# Sheet1.net
KiCad netlist of a schematic drawn in Altium Designer
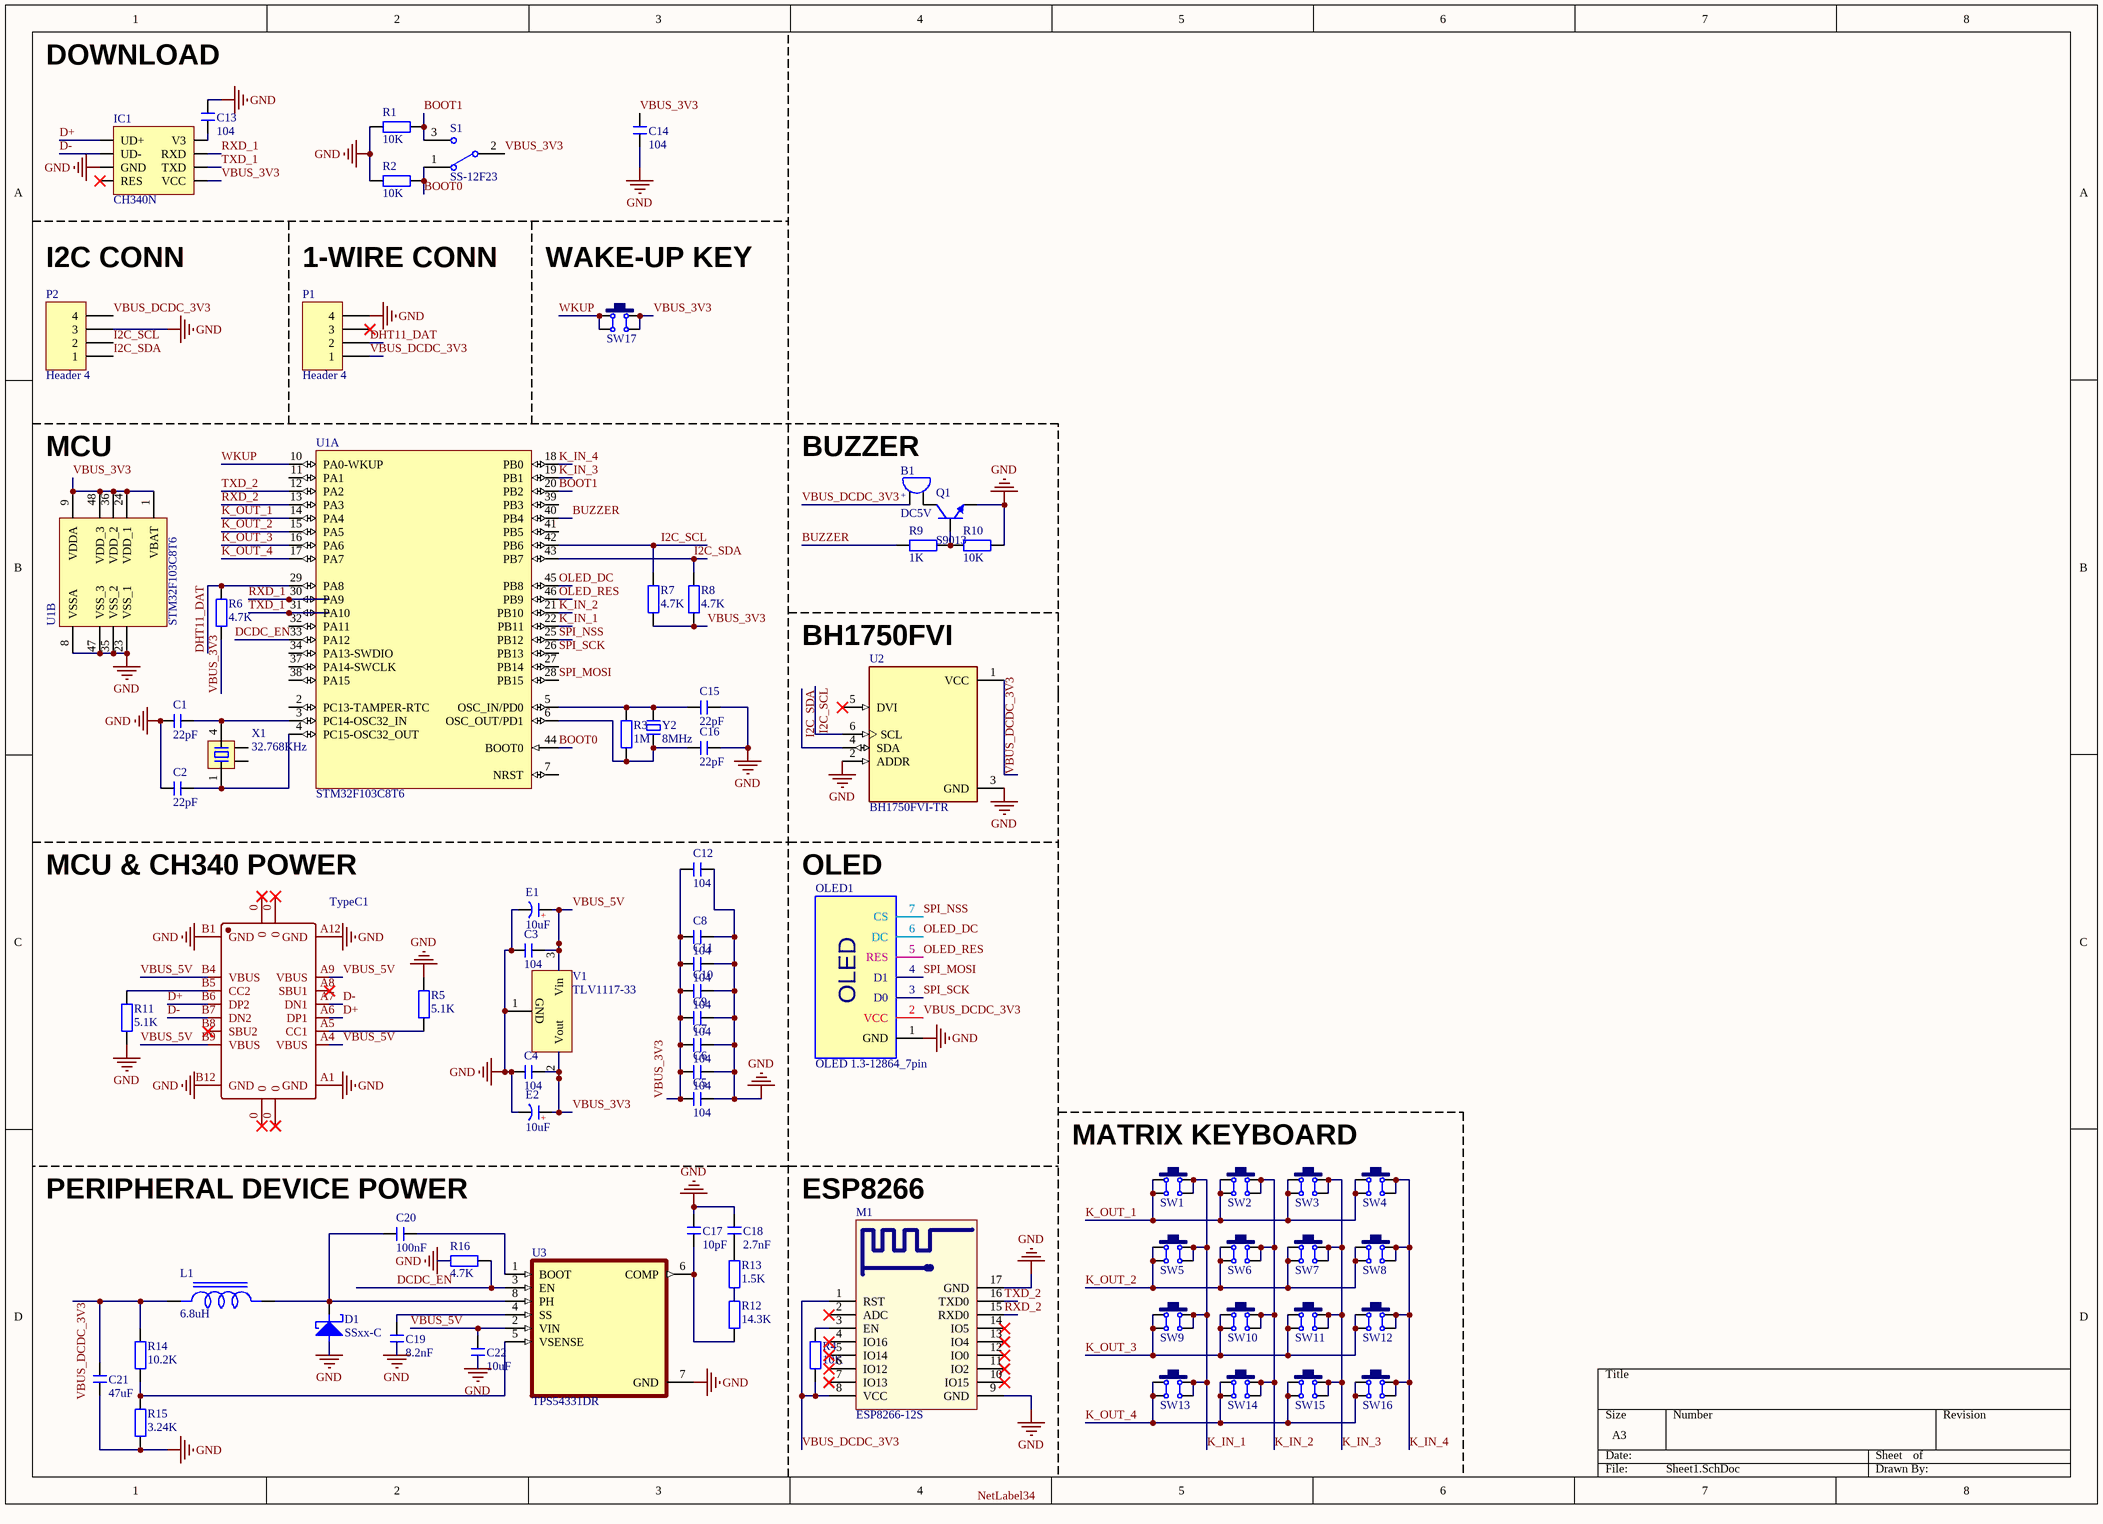
[diagram p0: Sheet1.SchDoc]

(export (version "E")
  (design (tool "Eeschema 10.0.6"))
  (components
    (comp (ref "B1")
      (value "DC5V")
      (footprint "BEEP 5x9x5.5")
      (description "蜂鸣器")
      (fields (field (name "版权归属") "黎明电子style"))
      (libsource (lib "基地硬件部AD库3.01") (part "BEEP"))
    )
    (comp (ref "C1")
      (value "22pF")
      (footprint "C 0805")
      (description "无极性贴片电容")
      (fields (field (name "版权归属") "黎明电子style"))
      (libsource (lib "基地硬件部AD库3.01") (part "C"))
    )
    (comp (ref "C2")
      (value "22pF")
      (footprint "C 0805")
      (description "无极性贴片电容")
      (fields (field (name "版权归属") "黎明电子style"))
      (libsource (lib "基地硬件部AD库3.01") (part "C"))
    )
    (comp (ref "C3")
      (value "104")
      (footprint "C 0805")
      (description "无极性贴片电容")
      (fields (field (name "版权归属") "黎明电子style"))
      (libsource (lib "基地硬件部AD库3.01") (part "C"))
    )
    (comp (ref "C4")
      (value "104")
      (footprint "C 0805")
      (description "无极性贴片电容")
      (fields (field (name "版权归属") "黎明电子style"))
      (libsource (lib "基地硬件部AD库3.01") (part "C"))
    )
    (comp (ref "C5")
      (value "104")
      (footprint "C 0805")
      (description "无极性贴片电容")
      (fields (field (name "版权归属") "黎明电子style"))
      (libsource (lib "基地硬件部AD库3.01") (part "C"))
    )
    (comp (ref "C6")
      (value "104")
      (footprint "C 0805")
      (description "无极性贴片电容")
      (fields (field (name "版权归属") "黎明电子style"))
      (libsource (lib "基地硬件部AD库3.01") (part "C"))
    )
    (comp (ref "C7")
      (value "104")
      (footprint "C 0805")
      (description "无极性贴片电容")
      (fields (field (name "版权归属") "黎明电子style"))
      (libsource (lib "基地硬件部AD库3.01") (part "C"))
    )
    (comp (ref "C8")
      (value "104")
      (footprint "C 0805")
      (description "无极性贴片电容")
      (fields (field (name "版权归属") "黎明电子style"))
      (libsource (lib "基地硬件部AD库3.01") (part "C"))
    )
    (comp (ref "C9")
      (value "104")
      (footprint "C 0805")
      (description "无极性贴片电容")
      (fields (field (name "版权归属") "黎明电子style"))
      (libsource (lib "基地硬件部AD库3.01") (part "C"))
    )
    (comp (ref "C10")
      (value "104")
      (footprint "C 0805")
      (description "无极性贴片电容")
      (fields (field (name "版权归属") "黎明电子style"))
      (libsource (lib "基地硬件部AD库3.01") (part "C"))
    )
    (comp (ref "C11")
      (value "104")
      (footprint "C 0805")
      (description "无极性贴片电容")
      (fields (field (name "版权归属") "黎明电子style"))
      (libsource (lib "基地硬件部AD库3.01") (part "C"))
    )
    (comp (ref "C12")
      (value "104")
      (footprint "C 0805")
      (description "无极性贴片电容")
      (fields (field (name "版权归属") "黎明电子style"))
      (libsource (lib "基地硬件部AD库3.01") (part "C"))
    )
    (comp (ref "C13")
      (value "104")
      (footprint "C 0805")
      (description "无极性贴片电容")
      (fields (field (name "版权归属") "黎明电子style"))
      (libsource (lib "基地硬件部AD库3.01") (part "C"))
    )
    (comp (ref "C14")
      (value "104")
      (footprint "C 0805")
      (description "无极性贴片电容")
      (fields (field (name "版权归属") "黎明电子style"))
      (libsource (lib "基地硬件部AD库3.01") (part "C"))
    )
    (comp (ref "C15")
      (value "22pF")
      (footprint "C 0805")
      (description "无极性贴片电容")
      (fields (field (name "版权归属") "黎明电子style"))
      (libsource (lib "基地硬件部AD库3.01") (part "C"))
    )
    (comp (ref "C16")
      (value "22pF")
      (footprint "C 0805")
      (description "无极性贴片电容")
      (fields (field (name "版权归属") "黎明电子style"))
      (libsource (lib "基地硬件部AD库3.01") (part "C"))
    )
    (comp (ref "C17")
      (value "10pF")
      (footprint "C 0805")
      (description "无极性贴片电容")
      (fields (field (name "版权归属") "黎明电子style"))
      (libsource (lib "基地硬件部AD库3.01") (part "C"))
    )
    (comp (ref "C18")
      (value "2.7nF")
      (footprint "C 0805")
      (description "无极性贴片电容")
      (fields (field (name "版权归属") "黎明电子style"))
      (libsource (lib "基地硬件部AD库3.01") (part "C"))
    )
    (comp (ref "C19")
      (value "8.2nF")
      (footprint "C 0805")
      (description "无极性贴片电容")
      (fields (field (name "版权归属") "黎明电子style"))
      (libsource (lib "基地硬件部AD库3.01") (part "C"))
    )
    (comp (ref "C20")
      (value "100nF")
      (footprint "C 0805")
      (description "无极性贴片电容")
      (fields (field (name "版权归属") "黎明电子style"))
      (libsource (lib "基地硬件部AD库3.01") (part "C"))
    )
    (comp (ref "C21")
      (value "47uF")
      (footprint "C 0805")
      (description "无极性贴片电容")
      (fields (field (name "版权归属") "黎明电子style"))
      (libsource (lib "基地硬件部AD库3.01") (part "C"))
    )
    (comp (ref "C22")
      (value "10uF")
      (footprint "C 0805")
      (description "无极性贴片电容")
      (fields (field (name "版权归属") "黎明电子style"))
      (libsource (lib "基地硬件部AD库3.01") (part "C"))
    )
    (comp (ref "D1")
      (value "SSxx-C")
      (footprint "SMA")
      (description "肖特基二极管-贴片")
      (libsource (lib "基地硬件部AD库3.01") (part "SSxx-C"))
    )
    (comp (ref "E1")
      (value "10uF")
      (footprint "CD A(3216)")
      (description "贴片钽电容")
      (fields (field (name "版权归属") "黎明电子style"))
      (libsource (lib "基地硬件部AD库3.01") (part "C-CD"))
    )
    (comp (ref "E2")
      (value "10uF")
      (footprint "CD A(3216)")
      (description "贴片钽电容")
      (fields (field (name "版权归属") "黎明电子style"))
      (libsource (lib "基地硬件部AD库3.01") (part "C-CD"))
    )
    (comp (ref "IC1")
      (value "CH340N")
      (footprint "SOP8_N")
      (description "串口转USB")
      (fields (field (name "版权归属") "黎明电子style"))
      (libsource (lib "基地硬件部AD库3.01") (part "CH340N"))
    )
    (comp (ref "L1")
      (value "6.8uH")
      (footprint "IND_SRR4818A-6R8Y")
      (fields (field (name "MP") "SRR4818A-6R8Y"))
      (libsource (lib "SRR4818A-6R8Y") (part "SRR4818A-6R8Y"))
    )
    (comp (ref "M1")
      (value "ESP8266-12S")
      (footprint "ESP-12S Module")
      (description "串口WIFI模块，ESP8266-12S")
      (libsource (lib "基地硬件部AD库3.01") (part "ESP8266-12S"))
    )
    (comp (ref "OLED1")
      (value "OLED 1.3-12864_7pin")
      (footprint "OLED 1.3-12864_7pin")
      (description "OLED-SPI")
      (libsource (lib "基地硬件部AD库3.01") (part "OLED-1.3-SPI"))
    )
    (comp (ref "P1")
      (value "Header 4")
      (footprint "HDR1X4")
      (description "Header, 4-Pin")
      (fields (field (name "PUBLISHER") "Altium Limited"))
      (libsource (lib "Miscellaneous Connectors") (part "Header 4"))
    )
    (comp (ref "P2")
      (value "Header 4")
      (footprint "HDR1X4")
      (description "Header, 4-Pin")
      (fields (field (name "PUBLISHER") "Altium Limited"))
      (libsource (lib "Miscellaneous Connectors") (part "Header 4"))
    )
    (comp (ref "Q1")
      (value "S9013")
      (footprint "SOT23-3N")
      (description "低频放大-NPN型")
      (fields (field (name "版权归属") "源创客"))
      (libsource (lib "基地硬件部AD库3.01") (part "9013-SMD"))
    )
    (comp (ref "R1")
      (value "10K")
      (footprint "R 0805")
      (description "贴片电阻")
      (fields (field (name "版权归属") "黎明电子style"))
      (libsource (lib "基地硬件部AD库3.01") (part "R"))
    )
    (comp (ref "R2")
      (value "10K")
      (footprint "R 0805")
      (description "贴片电阻")
      (fields (field (name "版权归属") "黎明电子style"))
      (libsource (lib "基地硬件部AD库3.01") (part "R"))
    )
    (comp (ref "R3")
      (value "1M")
      (footprint "R 0805")
      (description "贴片电阻")
      (fields (field (name "版权归属") "黎明电子style"))
      (libsource (lib "基地硬件部AD库3.01") (part "R"))
    )
    (comp (ref "R4")
      (value "10K")
      (footprint "R 0805")
      (description "贴片电阻")
      (fields (field (name "版权归属") "黎明电子style"))
      (libsource (lib "基地硬件部AD库3.01") (part "R"))
    )
    (comp (ref "R5")
      (value "5.1K")
      (footprint "R 0805")
      (description "贴片电阻")
      (fields (field (name "版权归属") "黎明电子style"))
      (libsource (lib "基地硬件部AD库3.01") (part "R"))
    )
    (comp (ref "R6")
      (value "4.7K")
      (footprint "R 0805")
      (description "贴片电阻")
      (fields (field (name "版权归属") "黎明电子style"))
      (libsource (lib "基地硬件部AD库3.01") (part "R"))
    )
    (comp (ref "R7")
      (value "4.7K")
      (footprint "R 0805")
      (description "贴片电阻")
      (fields (field (name "版权归属") "黎明电子style"))
      (libsource (lib "基地硬件部AD库3.01") (part "R"))
    )
    (comp (ref "R8")
      (value "4.7K")
      (footprint "R 0805")
      (description "贴片电阻")
      (fields (field (name "版权归属") "黎明电子style"))
      (libsource (lib "基地硬件部AD库3.01") (part "R"))
    )
    (comp (ref "R9")
      (value "1K")
      (footprint "R 0805")
      (description "贴片电阻")
      (fields (field (name "版权归属") "黎明电子style"))
      (libsource (lib "基地硬件部AD库3.01") (part "R"))
    )
    (comp (ref "R10")
      (value "10K")
      (footprint "R 0805")
      (description "贴片电阻")
      (fields (field (name "版权归属") "黎明电子style"))
      (libsource (lib "基地硬件部AD库3.01") (part "R"))
    )
    (comp (ref "R11")
      (value "5.1K")
      (footprint "R 0805")
      (description "贴片电阻")
      (fields (field (name "版权归属") "黎明电子style"))
      (libsource (lib "基地硬件部AD库3.01") (part "R"))
    )
    (comp (ref "R12")
      (value "14.3K")
      (footprint "R 0805")
      (description "贴片电阻")
      (fields (field (name "版权归属") "黎明电子style"))
      (libsource (lib "基地硬件部AD库3.01") (part "R"))
    )
    (comp (ref "R13")
      (value "1.5K")
      (footprint "R 0805")
      (description "贴片电阻")
      (fields (field (name "版权归属") "黎明电子style"))
      (libsource (lib "基地硬件部AD库3.01") (part "R"))
    )
    (comp (ref "R14")
      (value "10.2K")
      (footprint "R 0805")
      (description "贴片电阻")
      (fields (field (name "版权归属") "黎明电子style"))
      (libsource (lib "基地硬件部AD库3.01") (part "R"))
    )
    (comp (ref "R15")
      (value "3.24K")
      (footprint "R 0805")
      (description "贴片电阻")
      (fields (field (name "版权归属") "黎明电子style"))
      (libsource (lib "基地硬件部AD库3.01") (part "R"))
    )
    (comp (ref "R16")
      (value "4.7K")
      (footprint "R 0805")
      (description "贴片电阻")
      (fields (field (name "版权归属") "黎明电子style"))
      (libsource (lib "基地硬件部AD库3.01") (part "R"))
    )
    (comp (ref "S1")
      (value "SS-12F23")
      (footprint "MSK-12C01-07")
      (description "1路波动开关")
      (fields (field (name "版权归属") "黎明电子style"))
      (libsource (lib "基地硬件部AD库3.01") (part "SSW-1P"))
    )
    (comp (ref "SW1")
      (value "6x6x5")
      (footprint "TSW SMD-6*6*4.3")
      (description "贴片6x6轻触开关")
      (fields (field (name "版权归属") "黎明电子style"))
      (libsource (lib "基地硬件部AD库3.01") (part "TSW SMD-6x6"))
    )
    (comp (ref "SW2")
      (value "6x6x5")
      (footprint "TSW SMD-6*6*4.3")
      (description "贴片6x6轻触开关")
      (fields (field (name "版权归属") "黎明电子style"))
      (libsource (lib "基地硬件部AD库3.01") (part "TSW SMD-6x6"))
    )
    (comp (ref "SW3")
      (value "6x6x5")
      (footprint "TSW SMD-6*6*4.3")
      (description "贴片6x6轻触开关")
      (fields (field (name "版权归属") "黎明电子style"))
      (libsource (lib "基地硬件部AD库3.01") (part "TSW SMD-6x6"))
    )
    (comp (ref "SW4")
      (value "6x6x5")
      (footprint "TSW SMD-6*6*4.3")
      (description "贴片6x6轻触开关")
      (fields (field (name "版权归属") "黎明电子style"))
      (libsource (lib "基地硬件部AD库3.01") (part "TSW SMD-6x6"))
    )
    (comp (ref "SW5")
      (value "6x6x5")
      (footprint "TSW SMD-6*6*4.3")
      (description "贴片6x6轻触开关")
      (fields (field (name "版权归属") "黎明电子style"))
      (libsource (lib "基地硬件部AD库3.01") (part "TSW SMD-6x6"))
    )
    (comp (ref "SW6")
      (value "6x6x5")
      (footprint "TSW SMD-6*6*4.3")
      (description "贴片6x6轻触开关")
      (fields (field (name "版权归属") "黎明电子style"))
      (libsource (lib "基地硬件部AD库3.01") (part "TSW SMD-6x6"))
    )
    (comp (ref "SW7")
      (value "6x6x5")
      (footprint "TSW SMD-6*6*4.3")
      (description "贴片6x6轻触开关")
      (fields (field (name "版权归属") "黎明电子style"))
      (libsource (lib "基地硬件部AD库3.01") (part "TSW SMD-6x6"))
    )
    (comp (ref "SW8")
      (value "6x6x5")
      (footprint "TSW SMD-6*6*4.3")
      (description "贴片6x6轻触开关")
      (fields (field (name "版权归属") "黎明电子style"))
      (libsource (lib "基地硬件部AD库3.01") (part "TSW SMD-6x6"))
    )
    (comp (ref "SW9")
      (value "6x6x5")
      (footprint "TSW SMD-6*6*4.3")
      (description "贴片6x6轻触开关")
      (fields (field (name "版权归属") "黎明电子style"))
      (libsource (lib "基地硬件部AD库3.01") (part "TSW SMD-6x6"))
    )
    (comp (ref "SW10")
      (value "6x6x5")
      (footprint "TSW SMD-6*6*4.3")
      (description "贴片6x6轻触开关")
      (fields (field (name "版权归属") "黎明电子style"))
      (libsource (lib "基地硬件部AD库3.01") (part "TSW SMD-6x6"))
    )
    (comp (ref "SW11")
      (value "6x6x5")
      (footprint "TSW SMD-6*6*4.3")
      (description "贴片6x6轻触开关")
      (fields (field (name "版权归属") "黎明电子style"))
      (libsource (lib "基地硬件部AD库3.01") (part "TSW SMD-6x6"))
    )
    (comp (ref "SW12")
      (value "6x6x5")
      (footprint "TSW SMD-6*6*4.3")
      (description "贴片6x6轻触开关")
      (fields (field (name "版权归属") "黎明电子style"))
      (libsource (lib "基地硬件部AD库3.01") (part "TSW SMD-6x6"))
    )
    (comp (ref "SW13")
      (value "6x6x5")
      (footprint "TSW SMD-6*6*4.3")
      (description "贴片6x6轻触开关")
      (fields (field (name "版权归属") "黎明电子style"))
      (libsource (lib "基地硬件部AD库3.01") (part "TSW SMD-6x6"))
    )
    (comp (ref "SW14")
      (value "6x6x5")
      (footprint "TSW SMD-6*6*4.3")
      (description "贴片6x6轻触开关")
      (fields (field (name "版权归属") "黎明电子style"))
      (libsource (lib "基地硬件部AD库3.01") (part "TSW SMD-6x6"))
    )
    (comp (ref "SW15")
      (value "6x6x5")
      (footprint "TSW SMD-6*6*4.3")
      (description "贴片6x6轻触开关")
      (fields (field (name "版权归属") "黎明电子style"))
      (libsource (lib "基地硬件部AD库3.01") (part "TSW SMD-6x6"))
    )
    (comp (ref "SW16")
      (value "6x6x5")
      (footprint "TSW SMD-6*6*4.3")
      (description "贴片6x6轻触开关")
      (fields (field (name "版权归属") "黎明电子style"))
      (libsource (lib "基地硬件部AD库3.01") (part "TSW SMD-6x6"))
    )
    (comp (ref "SW17")
      (value "6x6x5")
      (footprint "TSW SMD-6*6*4.3")
      (description "贴片6x6轻触开关")
      (fields (field (name "版权归属") "黎明电子style"))
      (libsource (lib "基地硬件部AD库3.01") (part "TSW SMD-6x6"))
    )
    (comp (ref "TypeC1")
      (value "TypeC-16pin")
      (footprint "typeC-16pin")
      (description "USB-C-16Pin")
      (libsource (lib "基地硬件部AD库3.01") (part "TypeC-16pin"))
    )
    (comp (ref "U1")
      (value "STM32F103C8T6")
      (footprint "LQFP48 7X7_N")
      (description "Pin:48/IO:36")
      (fields (field (name "版权归属") "校基地硬件部"))
      (libsource (lib "") (part "STM32F103C8Tx_1"))
    )
    (comp (ref "U2")
      (value "BH1750FVI-TR")
      (footprint "XDCR_BH1750FVI-TR")
      (description "Light to Digital Ambient Light Sensor Digital O/P 1lux to 65535lux 6-Pin WSOF Embossed T/R")
      (libsource (lib "BH1750FVI-TR") (part "BH1750FVI-TR"))
    )
    (comp (ref "U3")
      (value "TPS54331DR")
      (footprint "SOIC127P599X175-8N")
      (description "3.5V to 28V Input, 3A, 570kHz Step-Down Converter with Eco-mode 8-SOIC -40 to 150")
      (fields (field (name "MF") "Texas Instruments"))
      (libsource (lib "TPS54331DR") (part "TPS54331DR"))
    )
    (comp (ref "V1")
      (value "TLV1117-33")
      (footprint "SOT223_L")
      (description "三端稳压芯片")
      (fields (field (name "版权归属") "源创客"))
      (libsource (lib "基地硬件部AD库3.01") (part "AMS1117"))
    )
    (comp (ref "X1")
      (value "32.768KHz")
      (footprint "OSC MC-146")
      (description "MC系列4脚晶振")
      (fields (field (name "版权归属") "源创客"))
      (libsource (lib "基地硬件部AD库3.01") (part "XTAL-MC-4P"))
    )
    (comp (ref "Y2")
      (value "8MHz")
      (footprint "OSC HC-49SMD")
      (description "2脚无源脚晶振")
      (fields (field (name "版权归属") "源创客"))
      (libsource (lib "基地硬件部AD库3.01") (part "XTAL-2P"))
    )
  )
  (nets
    (net (code "1") (name "/BOOT0") (class "Default")
      (node (ref "R2") (pin "2") (pinfunction "2_2") (pintype "passive"))
      (node (ref "S1") (pin "1") (pinfunction "1_1") (pintype "passive"))
      (node (ref "U1") (pin "44") (pinfunction "BOOT0_44") (pintype "input"))
    )
    (net (code "2") (name "/BOOT1") (class "Default")
      (node (ref "R1") (pin "2") (pinfunction "2_2") (pintype "passive"))
      (node (ref "S1") (pin "3") (pinfunction "3_3") (pintype "passive"))
      (node (ref "U1") (pin "20") (pinfunction "PB2_20") (pintype "bidirectional"))
    )
    (net (code "3") (name "/BUZZER") (class "Default")
      (node (ref "R9") (pin "2") (pinfunction "2_2") (pintype "passive"))
      (node (ref "U1") (pin "40") (pinfunction "PB4_40") (pintype "bidirectional"))
    )
    (net (code "4") (name "/D+") (class "Default")
      (node (ref "IC1") (pin "1") (pinfunction "UD+_1") (pintype "passive"))
      (node (ref "TypeC1") (pin "A6") (pinfunction "DP1_A6") (pintype "passive"))
      (node (ref "TypeC1") (pin "B6") (pinfunction "DP2_B6") (pintype "passive"))
    )
    (net (code "5") (name "/D-") (class "Default")
      (node (ref "IC1") (pin "2") (pinfunction "UD-_2") (pintype "passive"))
      (node (ref "TypeC1") (pin "A7") (pinfunction "DN1_A7") (pintype "passive"))
      (node (ref "TypeC1") (pin "B7") (pinfunction "DN2_B7") (pintype "passive"))
    )
    (net (code "6") (name "/DCDC_EN") (class "Default")
      (node (ref "R16") (pin "2") (pinfunction "2_2") (pintype "passive"))
      (node (ref "U1") (pin "33") (pinfunction "PA12_33") (pintype "bidirectional"))
      (node (ref "U3") (pin "3") (pinfunction "EN_3") (pintype "input"))
    )
    (net (code "7") (name "/DHT11_DAT") (class "Default")
      (node (ref "P1") (pin "2") (pinfunction "2_2") (pintype "passive"))
      (node (ref "R6") (pin "2") (pinfunction "2_2") (pintype "passive"))
      (node (ref "U1") (pin "29") (pinfunction "PA8_29") (pintype "bidirectional"))
    )
    (net (code "8") (name "/I2C_SCL") (class "Default")
      (node (ref "P2") (pin "2") (pinfunction "2_2") (pintype "passive"))
      (node (ref "R7") (pin "2") (pinfunction "2_2") (pintype "passive"))
      (node (ref "U1") (pin "42") (pinfunction "PB6_42") (pintype "bidirectional"))
      (node (ref "U2") (pin "6") (pinfunction "SCL_6") (pintype "input"))
    )
    (net (code "9") (name "/I2C_SDA") (class "Default")
      (node (ref "P2") (pin "1") (pinfunction "1_1") (pintype "passive"))
      (node (ref "R8") (pin "2") (pinfunction "2_2") (pintype "passive"))
      (node (ref "U1") (pin "43") (pinfunction "PB7_43") (pintype "bidirectional"))
      (node (ref "U2") (pin "4") (pinfunction "SDA_4") (pintype "bidirectional"))
    )
    (net (code "10") (name "/K_IN_1") (class "Default")
      (node (ref "SW1") (pin "2") (pinfunction "2_2") (pintype "passive"))
      (node (ref "SW1") (pin "3") (pinfunction "3_3") (pintype "passive"))
      (node (ref "SW13") (pin "2") (pinfunction "2_2") (pintype "passive"))
      (node (ref "SW13") (pin "3") (pinfunction "3_3") (pintype "passive"))
      (node (ref "SW5") (pin "2") (pinfunction "2_2") (pintype "passive"))
      (node (ref "SW5") (pin "3") (pinfunction "3_3") (pintype "passive"))
      (node (ref "SW9") (pin "2") (pinfunction "2_2") (pintype "passive"))
      (node (ref "SW9") (pin "3") (pinfunction "3_3") (pintype "passive"))
      (node (ref "U1") (pin "22") (pinfunction "PB11_22") (pintype "bidirectional"))
    )
    (net (code "11") (name "/K_IN_2") (class "Default")
      (node (ref "SW10") (pin "2") (pinfunction "2_2") (pintype "passive"))
      (node (ref "SW10") (pin "3") (pinfunction "3_3") (pintype "passive"))
      (node (ref "SW14") (pin "2") (pinfunction "2_2") (pintype "passive"))
      (node (ref "SW14") (pin "3") (pinfunction "3_3") (pintype "passive"))
      (node (ref "SW2") (pin "2") (pinfunction "2_2") (pintype "passive"))
      (node (ref "SW2") (pin "3") (pinfunction "3_3") (pintype "passive"))
      (node (ref "SW6") (pin "2") (pinfunction "2_2") (pintype "passive"))
      (node (ref "SW6") (pin "3") (pinfunction "3_3") (pintype "passive"))
      (node (ref "U1") (pin "21") (pinfunction "PB10_21") (pintype "bidirectional"))
    )
    (net (code "12") (name "/K_IN_3") (class "Default")
      (node (ref "SW11") (pin "2") (pinfunction "2_2") (pintype "passive"))
      (node (ref "SW11") (pin "3") (pinfunction "3_3") (pintype "passive"))
      (node (ref "SW15") (pin "2") (pinfunction "2_2") (pintype "passive"))
      (node (ref "SW15") (pin "3") (pinfunction "3_3") (pintype "passive"))
      (node (ref "SW3") (pin "2") (pinfunction "2_2") (pintype "passive"))
      (node (ref "SW3") (pin "3") (pinfunction "3_3") (pintype "passive"))
      (node (ref "SW7") (pin "2") (pinfunction "2_2") (pintype "passive"))
      (node (ref "SW7") (pin "3") (pinfunction "3_3") (pintype "passive"))
      (node (ref "U1") (pin "19") (pinfunction "PB1_19") (pintype "bidirectional"))
    )
    (net (code "13") (name "/K_IN_4") (class "Default")
      (node (ref "SW12") (pin "2") (pinfunction "2_2") (pintype "passive"))
      (node (ref "SW12") (pin "3") (pinfunction "3_3") (pintype "passive"))
      (node (ref "SW16") (pin "2") (pinfunction "2_2") (pintype "passive"))
      (node (ref "SW16") (pin "3") (pinfunction "3_3") (pintype "passive"))
      (node (ref "SW4") (pin "2") (pinfunction "2_2") (pintype "passive"))
      (node (ref "SW4") (pin "3") (pinfunction "3_3") (pintype "passive"))
      (node (ref "SW8") (pin "2") (pinfunction "2_2") (pintype "passive"))
      (node (ref "SW8") (pin "3") (pinfunction "3_3") (pintype "passive"))
      (node (ref "U1") (pin "18") (pinfunction "PB0_18") (pintype "bidirectional"))
    )
    (net (code "14") (name "/K_OUT_1") (class "Default")
      (node (ref "SW1") (pin "1") (pinfunction "1_1") (pintype "passive"))
      (node (ref "SW1") (pin "4") (pinfunction "4_4") (pintype "passive"))
      (node (ref "SW2") (pin "1") (pinfunction "1_1") (pintype "passive"))
      (node (ref "SW2") (pin "4") (pinfunction "4_4") (pintype "passive"))
      (node (ref "SW3") (pin "1") (pinfunction "1_1") (pintype "passive"))
      (node (ref "SW3") (pin "4") (pinfunction "4_4") (pintype "passive"))
      (node (ref "SW4") (pin "1") (pinfunction "1_1") (pintype "passive"))
      (node (ref "SW4") (pin "4") (pinfunction "4_4") (pintype "passive"))
      (node (ref "U1") (pin "14") (pinfunction "PA4_14") (pintype "bidirectional"))
    )
    (net (code "15") (name "/K_OUT_2") (class "Default")
      (node (ref "SW5") (pin "1") (pinfunction "1_1") (pintype "passive"))
      (node (ref "SW5") (pin "4") (pinfunction "4_4") (pintype "passive"))
      (node (ref "SW6") (pin "1") (pinfunction "1_1") (pintype "passive"))
      (node (ref "SW6") (pin "4") (pinfunction "4_4") (pintype "passive"))
      (node (ref "SW7") (pin "1") (pinfunction "1_1") (pintype "passive"))
      (node (ref "SW7") (pin "4") (pinfunction "4_4") (pintype "passive"))
      (node (ref "SW8") (pin "1") (pinfunction "1_1") (pintype "passive"))
      (node (ref "SW8") (pin "4") (pinfunction "4_4") (pintype "passive"))
      (node (ref "U1") (pin "15") (pinfunction "PA5_15") (pintype "bidirectional"))
    )
    (net (code "16") (name "/K_OUT_3") (class "Default")
      (node (ref "SW10") (pin "1") (pinfunction "1_1") (pintype "passive"))
      (node (ref "SW10") (pin "4") (pinfunction "4_4") (pintype "passive"))
      (node (ref "SW11") (pin "1") (pinfunction "1_1") (pintype "passive"))
      (node (ref "SW11") (pin "4") (pinfunction "4_4") (pintype "passive"))
      (node (ref "SW12") (pin "1") (pinfunction "1_1") (pintype "passive"))
      (node (ref "SW12") (pin "4") (pinfunction "4_4") (pintype "passive"))
      (node (ref "SW9") (pin "1") (pinfunction "1_1") (pintype "passive"))
      (node (ref "SW9") (pin "4") (pinfunction "4_4") (pintype "passive"))
      (node (ref "U1") (pin "16") (pinfunction "PA6_16") (pintype "bidirectional"))
    )
    (net (code "17") (name "/K_OUT_4") (class "Default")
      (node (ref "SW13") (pin "1") (pinfunction "1_1") (pintype "passive"))
      (node (ref "SW13") (pin "4") (pinfunction "4_4") (pintype "passive"))
      (node (ref "SW14") (pin "1") (pinfunction "1_1") (pintype "passive"))
      (node (ref "SW14") (pin "4") (pinfunction "4_4") (pintype "passive"))
      (node (ref "SW15") (pin "1") (pinfunction "1_1") (pintype "passive"))
      (node (ref "SW15") (pin "4") (pinfunction "4_4") (pintype "passive"))
      (node (ref "SW16") (pin "1") (pinfunction "1_1") (pintype "passive"))
      (node (ref "SW16") (pin "4") (pinfunction "4_4") (pintype "passive"))
      (node (ref "U1") (pin "17") (pinfunction "PA7_17") (pintype "bidirectional"))
    )
    (net (code "19") (name "/OLED_DC") (class "Default")
      (node (ref "OLED1") (pin "6") (pinfunction "DC_6") (pintype "passive"))
      (node (ref "U1") (pin "45") (pinfunction "PB8_45") (pintype "bidirectional"))
    )
    (net (code "20") (name "/OLED_RES") (class "Default")
      (node (ref "OLED1") (pin "5") (pinfunction "RES_5") (pintype "passive"))
      (node (ref "U1") (pin "46") (pinfunction "PB9_46") (pintype "bidirectional"))
    )
    (net (code "21") (name "/RXD_1") (class "Default")
      (node (ref "IC1") (pin "7") (pinfunction "RXD_7") (pintype "passive"))
      (node (ref "U1") (pin "30") (pinfunction "PA9_30") (pintype "bidirectional"))
    )
    (net (code "22") (name "/RXD_2") (class "Default")
      (node (ref "M1") (pin "15") (pinfunction "RXD0_15") (pintype "passive"))
      (node (ref "U1") (pin "13") (pinfunction "PA3_13") (pintype "bidirectional"))
    )
    (net (code "23") (name "/SPI_MOSI") (class "Default")
      (node (ref "OLED1") (pin "4") (pinfunction "D1_4") (pintype "passive"))
      (node (ref "U1") (pin "28") (pinfunction "PB15_28") (pintype "bidirectional"))
    )
    (net (code "24") (name "/SPI_NSS") (class "Default")
      (node (ref "OLED1") (pin "7") (pinfunction "CS_7") (pintype "passive"))
      (node (ref "U1") (pin "25") (pinfunction "PB12_25") (pintype "bidirectional"))
    )
    (net (code "25") (name "/SPI_SCK") (class "Default")
      (node (ref "OLED1") (pin "3") (pinfunction "D0_3") (pintype "passive"))
      (node (ref "U1") (pin "26") (pinfunction "PB13_26") (pintype "bidirectional"))
    )
    (net (code "26") (name "/TXD_1") (class "Default")
      (node (ref "IC1") (pin "6") (pinfunction "TXD_6") (pintype "passive"))
      (node (ref "U1") (pin "31") (pinfunction "PA10_31") (pintype "bidirectional"))
    )
    (net (code "27") (name "/TXD_2") (class "Default")
      (node (ref "M1") (pin "16") (pinfunction "TXD0_16") (pintype "passive"))
      (node (ref "U1") (pin "12") (pinfunction "PA2_12") (pintype "bidirectional"))
    )
    (net (code "28") (name "/VBUS_3V3") (class "Default")
      (node (ref "C10") (pin "1") (pinfunction "1_1") (pintype "passive"))
      (node (ref "C11") (pin "1") (pinfunction "1_1") (pintype "passive"))
      (node (ref "C12") (pin "1") (pinfunction "1_1") (pintype "passive"))
      (node (ref "C14") (pin "1") (pinfunction "1_1") (pintype "passive"))
      (node (ref "C4") (pin "1") (pinfunction "1_1") (pintype "passive"))
      (node (ref "C5") (pin "1") (pinfunction "1_1") (pintype "passive"))
      (node (ref "C6") (pin "1") (pinfunction "1_1") (pintype "passive"))
      (node (ref "C7") (pin "1") (pinfunction "1_1") (pintype "passive"))
      (node (ref "C8") (pin "1") (pinfunction "1_1") (pintype "passive"))
      (node (ref "C9") (pin "1") (pinfunction "1_1") (pintype "passive"))
      (node (ref "E2") (pin "1") (pinfunction "A_1") (pintype "passive"))
      (node (ref "IC1") (pin "5") (pinfunction "VCC_5") (pintype "passive"))
      (node (ref "R6") (pin "1") (pinfunction "1_1") (pintype "passive"))
      (node (ref "R7") (pin "1") (pinfunction "1_1") (pintype "passive"))
      (node (ref "R8") (pin "1") (pinfunction "1_1") (pintype "passive"))
      (node (ref "S1") (pin "2") (pinfunction "2_2") (pintype "passive"))
      (node (ref "SW17") (pin "2") (pinfunction "2_2") (pintype "passive"))
      (node (ref "SW17") (pin "3") (pinfunction "3_3") (pintype "passive"))
      (node (ref "U1") (pin "1") (pinfunction "VBAT_1") (pintype "power_in"))
      (node (ref "U1") (pin "24") (pinfunction "VDD_1_24") (pintype "power_in"))
      (node (ref "U1") (pin "36") (pinfunction "VDD_2_36") (pintype "power_in"))
      (node (ref "U1") (pin "48") (pinfunction "VDD_3_48") (pintype "power_in"))
      (node (ref "U1") (pin "9") (pinfunction "VDDA_9") (pintype "power_in"))
      (node (ref "V1") (pin "2") (pinfunction "Vout_2") (pintype "passive"))
    )
    (net (code "29") (name "/VBUS_5V") (class "Default")
      (node (ref "C22") (pin "2") (pinfunction "2_2") (pintype "passive"))
      (node (ref "C3") (pin "1") (pinfunction "1_1") (pintype "passive"))
      (node (ref "E1") (pin "1") (pinfunction "A_1") (pintype "passive"))
      (node (ref "TypeC1") (pin "A4") (pinfunction "VBUS_A4") (pintype "passive"))
      (node (ref "TypeC1") (pin "A9") (pinfunction "VBUS_A9") (pintype "passive"))
      (node (ref "TypeC1") (pin "B4") (pinfunction "VBUS_B4") (pintype "passive"))
      (node (ref "TypeC1") (pin "B9") (pinfunction "VBUS_B9") (pintype "passive"))
      (node (ref "U3") (pin "2") (pinfunction "VIN_2") (pintype "input"))
      (node (ref "V1") (pin "3") (pinfunction "Vin_3") (pintype "passive"))
    )
    (net (code "30") (name "/VBUS_DCDC_3V3") (class "Default")
      (node (ref "B1") (pin "1") (pinfunction "1_1") (pintype "passive"))
      (node (ref "C21") (pin "2") (pinfunction "2_2") (pintype "passive"))
      (node (ref "L1") (pin "1") (pinfunction "1_1") (pintype "passive"))
      (node (ref "M1") (pin "1") (pinfunction "RST_1") (pintype "passive"))
      (node (ref "M1") (pin "8") (pinfunction "VCC_8") (pintype "passive"))
      (node (ref "OLED1") (pin "2") (pinfunction "VCC_2") (pintype "passive"))
      (node (ref "P1") (pin "1") (pinfunction "1_1") (pintype "passive"))
      (node (ref "P2") (pin "4") (pinfunction "4_4") (pintype "passive"))
      (node (ref "R14") (pin "1") (pinfunction "1_1") (pintype "passive"))
      (node (ref "R4") (pin "1") (pinfunction "1_1") (pintype "passive"))
      (node (ref "U2") (pin "1") (pinfunction "VCC_1") (pintype "power_in"))
    )
    (net (code "31") (name "/WKUP") (class "Default")
      (node (ref "SW17") (pin "1") (pinfunction "1_1") (pintype "passive"))
      (node (ref "SW17") (pin "4") (pinfunction "4_4") (pintype "passive"))
      (node (ref "U1") (pin "10") (pinfunction "PA0-WKUP_10") (pintype "bidirectional"))
    )
    (net (code "32") (name "GND") (class "Default")
      (node (ref "C1") (pin "2") (pinfunction "2_2") (pintype "passive"))
      (node (ref "C10") (pin "2") (pinfunction "2_2") (pintype "passive"))
      (node (ref "C11") (pin "2") (pinfunction "2_2") (pintype "passive"))
      (node (ref "C12") (pin "2") (pinfunction "2_2") (pintype "passive"))
      (node (ref "C13") (pin "1") (pinfunction "1_1") (pintype "passive"))
      (node (ref "C14") (pin "2") (pinfunction "2_2") (pintype "passive"))
      (node (ref "C15") (pin "1") (pinfunction "1_1") (pintype "passive"))
      (node (ref "C16") (pin "1") (pinfunction "1_1") (pintype "passive"))
      (node (ref "C17") (pin "2") (pinfunction "2_2") (pintype "passive"))
      (node (ref "C18") (pin "2") (pinfunction "2_2") (pintype "passive"))
      (node (ref "C19") (pin "1") (pinfunction "1_1") (pintype "passive"))
      (node (ref "C2") (pin "2") (pinfunction "2_2") (pintype "passive"))
      (node (ref "C21") (pin "1") (pinfunction "1_1") (pintype "passive"))
      (node (ref "C22") (pin "1") (pinfunction "1_1") (pintype "passive"))
      (node (ref "C3") (pin "2") (pinfunction "2_2") (pintype "passive"))
      (node (ref "C4") (pin "2") (pinfunction "2_2") (pintype "passive"))
      (node (ref "C5") (pin "2") (pinfunction "2_2") (pintype "passive"))
      (node (ref "C6") (pin "2") (pinfunction "2_2") (pintype "passive"))
      (node (ref "C7") (pin "2") (pinfunction "2_2") (pintype "passive"))
      (node (ref "C8") (pin "2") (pinfunction "2_2") (pintype "passive"))
      (node (ref "C9") (pin "2") (pinfunction "2_2") (pintype "passive"))
      (node (ref "D1") (pin "1") (pinfunction "A_1") (pintype "passive"))
      (node (ref "E1") (pin "2") (pinfunction "K_2") (pintype "passive"))
      (node (ref "E2") (pin "2") (pinfunction "K_2") (pintype "passive"))
      (node (ref "IC1") (pin "3") (pinfunction "GND_3") (pintype "passive"))
      (node (ref "M1") (pin "17") (pinfunction "GND_17") (pintype "passive"))
      (node (ref "M1") (pin "9") (pinfunction "GND_9") (pintype "passive"))
      (node (ref "OLED1") (pin "1") (pinfunction "GND_1") (pintype "passive"))
      (node (ref "P1") (pin "4") (pinfunction "4_4") (pintype "passive"))
      (node (ref "P2") (pin "3") (pinfunction "3_3") (pintype "passive"))
      (node (ref "Q1") (pin "2") (pinfunction "E_2") (pintype "passive"))
      (node (ref "R1") (pin "1") (pinfunction "1_1") (pintype "passive"))
      (node (ref "R10") (pin "1") (pinfunction "1_1") (pintype "passive"))
      (node (ref "R11") (pin "1") (pinfunction "1_1") (pintype "passive"))
      (node (ref "R15") (pin "2") (pinfunction "2_2") (pintype "passive"))
      (node (ref "R16") (pin "1") (pinfunction "1_1") (pintype "passive"))
      (node (ref "R2") (pin "1") (pinfunction "1_1") (pintype "passive"))
      (node (ref "R5") (pin "1") (pinfunction "1_1") (pintype "passive"))
      (node (ref "TypeC1") (pin "A1") (pinfunction "GND_A1") (pintype "passive"))
      (node (ref "TypeC1") (pin "A12") (pinfunction "GND_A12") (pintype "passive"))
      (node (ref "TypeC1") (pin "B1") (pinfunction "GND_B1") (pintype "passive"))
      (node (ref "TypeC1") (pin "B12") (pinfunction "GND_B12") (pintype "passive"))
      (node (ref "U1") (pin "23") (pinfunction "VSS_1_23") (pintype "power_in"))
      (node (ref "U1") (pin "35") (pinfunction "VSS_2_35") (pintype "power_in"))
      (node (ref "U1") (pin "47") (pinfunction "VSS_3_47") (pintype "power_in"))
      (node (ref "U1") (pin "8") (pinfunction "VSSA_8") (pintype "power_in"))
      (node (ref "U2") (pin "2") (pinfunction "ADDR_2") (pintype "input"))
      (node (ref "U2") (pin "3") (pinfunction "GND_3") (pintype "power_in"))
      (node (ref "U3") (pin "7") (pinfunction "GND_7") (pintype "power_in"))
      (node (ref "V1") (pin "1") (pinfunction "GND_1") (pintype "passive"))
    )
    (net (code "33") (name "Net-(C18-Pad1)") (class "Default")
      (node (ref "C18") (pin "1") (pinfunction "1_1") (pintype "passive"))
      (node (ref "R13") (pin "1") (pinfunction "1_1") (pintype "passive"))
    )
    (net (code "34") (name "Net-(D1-K)") (class "Default")
      (node (ref "C20") (pin "1") (pinfunction "1_1") (pintype "passive"))
      (node (ref "D1") (pin "2") (pinfunction "K_2") (pintype "passive"))
      (node (ref "L1") (pin "2") (pinfunction "2_2") (pintype "passive"))
      (node (ref "U3") (pin "8") (pinfunction "PH_8") (pintype "input"))
    )
    (net (code "35") (name "Net-(IC1-V3)") (class "Default")
      (node (ref "C13") (pin "2") (pinfunction "2_2") (pintype "passive"))
      (node (ref "IC1") (pin "8") (pinfunction "V3_8") (pintype "passive"))
    )
    (net (code "36") (name "Net-(M1-EN)") (class "Default")
      (node (ref "M1") (pin "3") (pinfunction "EN_3") (pintype "passive"))
      (node (ref "R4") (pin "2") (pinfunction "2_2") (pintype "passive"))
    )
    (net (code "37") (name "Net-(Q1-B)") (class "Default")
      (node (ref "Q1") (pin "1") (pinfunction "B_1") (pintype "passive"))
      (node (ref "R10") (pin "2") (pinfunction "2_2") (pintype "passive"))
      (node (ref "R9") (pin "1") (pinfunction "1_1") (pintype "passive"))
    )
    (net (code "38") (name "Net-(Q1-C)") (class "Default")
      (node (ref "B1") (pin "2") (pinfunction "2_2") (pintype "passive"))
      (node (ref "Q1") (pin "3") (pinfunction "C_3") (pintype "passive"))
    )
    (net (code "39") (name "Net-(R12-Pad1)") (class "Default")
      (node (ref "R12") (pin "1") (pinfunction "1_1") (pintype "passive"))
      (node (ref "R13") (pin "2") (pinfunction "2_2") (pintype "passive"))
    )
    (net (code "40") (name "Net-(TypeC1-CC1)") (class "Default")
      (node (ref "R5") (pin "2") (pinfunction "2_2") (pintype "passive"))
      (node (ref "TypeC1") (pin "A5") (pinfunction "CC1_A5") (pintype "passive"))
    )
    (net (code "41") (name "Net-(TypeC1-CC2)") (class "Default")
      (node (ref "R11") (pin "2") (pinfunction "2_2") (pintype "passive"))
      (node (ref "TypeC1") (pin "B5") (pinfunction "CC2_B5") (pintype "passive"))
    )
    (net (code "42") (name "Net-(U1A-OSC_IN{slash}PD0)") (class "Default")
      (node (ref "C15") (pin "2") (pinfunction "2_2") (pintype "passive"))
      (node (ref "R3") (pin "2") (pinfunction "2_2") (pintype "passive"))
      (node (ref "U1") (pin "5") (pinfunction "OSC_IN/PD0_5") (pintype "bidirectional"))
      (node (ref "Y2") (pin "2") (pinfunction "2_2") (pintype "passive"))
    )
    (net (code "43") (name "Net-(U1A-OSC_OUT{slash}PD1)") (class "Default")
      (node (ref "C16") (pin "2") (pinfunction "2_2") (pintype "passive"))
      (node (ref "R3") (pin "1") (pinfunction "1_1") (pintype "passive"))
      (node (ref "U1") (pin "6") (pinfunction "OSC_OUT/PD1_6") (pintype "bidirectional"))
      (node (ref "Y2") (pin "1") (pinfunction "1_1") (pintype "passive"))
    )
    (net (code "44") (name "Net-(U1A-PC14-OSC32_IN)") (class "Default")
      (node (ref "C1") (pin "1") (pinfunction "1_1") (pintype "passive"))
      (node (ref "U1") (pin "3") (pinfunction "PC14-OSC32_IN_3") (pintype "bidirectional"))
      (node (ref "X1") (pin "4") (pinfunction "4_4") (pintype "passive"))
    )
    (net (code "45") (name "Net-(U1A-PC15-OSC32_OUT)") (class "Default")
      (node (ref "C2") (pin "1") (pinfunction "1_1") (pintype "passive"))
      (node (ref "U1") (pin "4") (pinfunction "PC15-OSC32_OUT_4") (pintype "bidirectional"))
      (node (ref "X1") (pin "1") (pinfunction "1_1") (pintype "passive"))
    )
    (net (code "46") (name "Net-(U3-BOOT)") (class "Default")
      (node (ref "C20") (pin "2") (pinfunction "2_2") (pintype "passive"))
      (node (ref "U3") (pin "1") (pinfunction "BOOT_1") (pintype "input"))
    )
    (net (code "47") (name "Net-(U3-COMP)") (class "Default")
      (node (ref "C17") (pin "1") (pinfunction "1_1") (pintype "passive"))
      (node (ref "R12") (pin "2") (pinfunction "2_2") (pintype "passive"))
      (node (ref "U3") (pin "6") (pinfunction "COMP_6") (pintype "output"))
    )
    (net (code "48") (name "Net-(U3-SS)") (class "Default")
      (node (ref "C19") (pin "2") (pinfunction "2_2") (pintype "passive"))
      (node (ref "U3") (pin "4") (pinfunction "SS_4") (pintype "input"))
    )
    (net (code "49") (name "Net-(U3-VSENSE)") (class "Default")
      (node (ref "R14") (pin "2") (pinfunction "2_2") (pintype "passive"))
      (node (ref "R15") (pin "1") (pinfunction "1_1") (pintype "passive"))
      (node (ref "U3") (pin "5") (pinfunction "VSENSE_5") (pintype "input"))
    )
    (net (code "50") (name "unconnected-(IC1-RES-Pad4)") (class "Default")
      (node (ref "IC1") (pin "4") (pinfunction "RES_4") (pintype "passive+no_connect"))
    )
    (net (code "51") (name "unconnected-(M1-ADC-Pad2)") (class "Default")
      (node (ref "M1") (pin "2") (pinfunction "ADC_2") (pintype "passive+no_connect"))
    )
    (net (code "52") (name "unconnected-(M1-IO0-Pad12)") (class "Default")
      (node (ref "M1") (pin "12") (pinfunction "IO0_12") (pintype "passive+no_connect"))
    )
    (net (code "53") (name "unconnected-(M1-IO2-Pad11)") (class "Default")
      (node (ref "M1") (pin "11") (pinfunction "IO2_11") (pintype "passive+no_connect"))
    )
    (net (code "54") (name "unconnected-(M1-IO4-Pad13)") (class "Default")
      (node (ref "M1") (pin "13") (pinfunction "IO4_13") (pintype "passive+no_connect"))
    )
    (net (code "55") (name "unconnected-(M1-IO5-Pad14)") (class "Default")
      (node (ref "M1") (pin "14") (pinfunction "IO5_14") (pintype "passive+no_connect"))
    )
    (net (code "56") (name "unconnected-(M1-IO12-Pad6)") (class "Default")
      (node (ref "M1") (pin "6") (pinfunction "IO12_6") (pintype "passive+no_connect"))
    )
    (net (code "57") (name "unconnected-(M1-IO13-Pad7)") (class "Default")
      (node (ref "M1") (pin "7") (pinfunction "IO13_7") (pintype "passive+no_connect"))
    )
    (net (code "58") (name "unconnected-(M1-IO14-Pad5)") (class "Default")
      (node (ref "M1") (pin "5") (pinfunction "IO14_5") (pintype "passive+no_connect"))
    )
    (net (code "59") (name "unconnected-(M1-IO15-Pad10)") (class "Default")
      (node (ref "M1") (pin "10") (pinfunction "IO15_10") (pintype "passive+no_connect"))
    )
    (net (code "60") (name "unconnected-(M1-IO16-Pad4)") (class "Default")
      (node (ref "M1") (pin "4") (pinfunction "IO16_4") (pintype "passive+no_connect"))
    )
    (net (code "61") (name "unconnected-(P1-Pad3)") (class "Default")
      (node (ref "P1") (pin "3") (pinfunction "3_3") (pintype "passive+no_connect"))
    )
    (net (code "62") (name "unconnected-(TypeC1-Pad0)") (class "Default")
      (node (ref "TypeC1") (pin "0") (pinfunction "0_0") (pintype "passive+no_connect"))
    )
    (net (code "63") (name "unconnected-(TypeC1-Pad0)_1") (class "Default")
      (node (ref "TypeC1") (pin "0") (pinfunction "0_0") (pintype "passive+no_connect"))
    )
    (net (code "64") (name "unconnected-(TypeC1-Pad0)_2") (class "Default")
      (node (ref "TypeC1") (pin "0") (pinfunction "0_0") (pintype "passive+no_connect"))
    )
    (net (code "65") (name "unconnected-(TypeC1-Pad0)_3") (class "Default")
      (node (ref "TypeC1") (pin "0") (pinfunction "0_0") (pintype "passive+no_connect"))
    )
    (net (code "66") (name "unconnected-(TypeC1-SBU1-PadA8)") (class "Default")
      (node (ref "TypeC1") (pin "A8") (pinfunction "SBU1_A8") (pintype "passive+no_connect"))
    )
    (net (code "67") (name "unconnected-(TypeC1-SBU2-PadB8)") (class "Default")
      (node (ref "TypeC1") (pin "B8") (pinfunction "SBU2_B8") (pintype "passive+no_connect"))
    )
    (net (code "68") (name "unconnected-(U1A-NRST-Pad7)") (class "Default")
      (node (ref "U1") (pin "7") (pinfunction "NRST_7") (pintype "bidirectional"))
    )
    (net (code "69") (name "unconnected-(U1A-PA1-Pad11)") (class "Default")
      (node (ref "U1") (pin "11") (pinfunction "PA1_11") (pintype "bidirectional"))
    )
    (net (code "70") (name "unconnected-(U1A-PA11-Pad32)") (class "Default")
      (node (ref "U1") (pin "32") (pinfunction "PA11_32") (pintype "bidirectional"))
    )
    (net (code "71") (name "unconnected-(U1A-PA13-SWDIO-Pad34)") (class "Default")
      (node (ref "U1") (pin "34") (pinfunction "PA13-SWDIO_34") (pintype "bidirectional"))
    )
    (net (code "72") (name "unconnected-(U1A-PA14-SWCLK-Pad37)") (class "Default")
      (node (ref "U1") (pin "37") (pinfunction "PA14-SWCLK_37") (pintype "bidirectional"))
    )
    (net (code "73") (name "unconnected-(U1A-PA15-Pad38)") (class "Default")
      (node (ref "U1") (pin "38") (pinfunction "PA15_38") (pintype "bidirectional"))
    )
    (net (code "74") (name "unconnected-(U1A-PB3-Pad39)") (class "Default")
      (node (ref "U1") (pin "39") (pinfunction "PB3_39") (pintype "bidirectional"))
    )
    (net (code "75") (name "unconnected-(U1A-PB5-Pad41)") (class "Default")
      (node (ref "U1") (pin "41") (pinfunction "PB5_41") (pintype "bidirectional"))
    )
    (net (code "76") (name "unconnected-(U1A-PB14-Pad27)") (class "Default")
      (node (ref "U1") (pin "27") (pinfunction "PB14_27") (pintype "bidirectional"))
    )
    (net (code "77") (name "unconnected-(U1A-PC13-TAMPER-RTC-Pad2)") (class "Default")
      (node (ref "U1") (pin "2") (pinfunction "PC13-TAMPER-RTC_2") (pintype "bidirectional"))
    )
    (net (code "78") (name "unconnected-(U2-DVI-Pad5)") (class "Default")
      (node (ref "U2") (pin "5") (pinfunction "DVI_5") (pintype "input+no_connect"))
    )
    (net (code "79") (name "unconnected-(X1-Pad2)") (class "Default")
      (node (ref "X1") (pin "2") (pinfunction "2_2") (pintype "passive"))
    )
    (net (code "80") (name "unconnected-(X1-Pad3)") (class "Default")
      (node (ref "X1") (pin "3") (pinfunction "3_3") (pintype "passive"))
    )
  )
)
